# BiphasicBoard.net
KiCad netlist of a schematic drawn in EAGLE
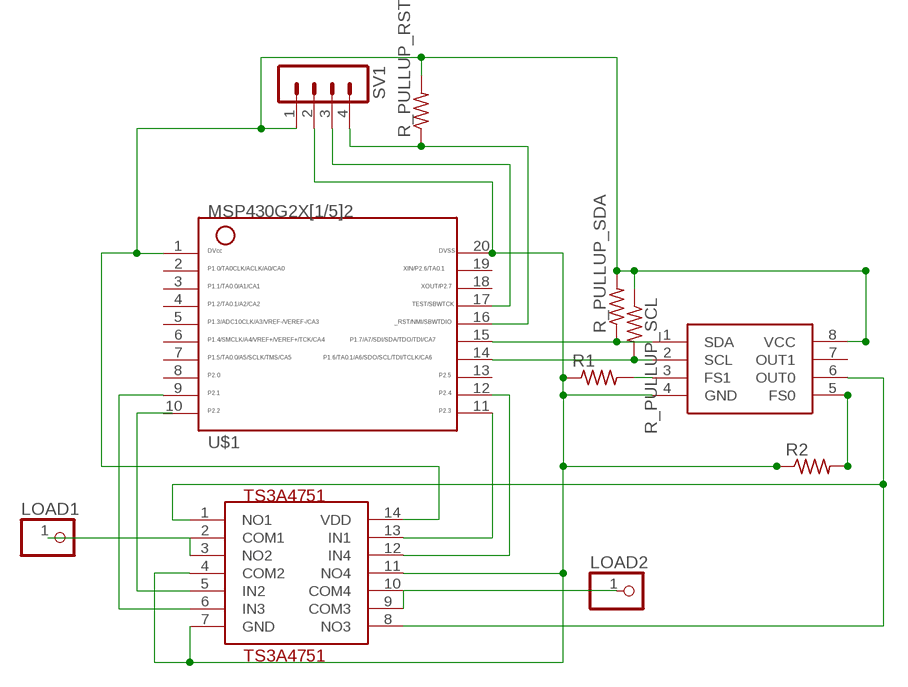
[diagram p0: schematic, sheet 1]

(export (version "E")
  (design (tool "Eeschema 10.0.6"))
  (components
    (comp (ref "DS4432")
      (value "DS4432U+")
      (footprint "eagle-import:DS4432U+")
      (libsource (lib "eagle-import") (part "DS4432U+"))
    )
    (comp (ref "LOAD1")
      (value "PINHD-1X1")
      (footprint "eagle-import:1X01")
      (libsource (lib "eagle-import") (part "PINHD-1X1"))
    )
    (comp (ref "LOAD2")
      (value "PINHD-1X1")
      (footprint "eagle-import:1X01")
      (libsource (lib "eagle-import") (part "PINHD-1X1"))
    )
    (comp (ref "R1")
      (value "R-US_R0603")
      (footprint "eagle-import:R0603")
      (libsource (lib "eagle-import") (part "R-US_R0603"))
    )
    (comp (ref "R2")
      (value "R-US_R0603")
      (footprint "eagle-import:R0603")
      (libsource (lib "eagle-import") (part "R-US_R0603"))
    )
    (comp (ref "R_PULLUP_RST")
      (value "R-US_R0603")
      (footprint "eagle-import:R0603")
      (libsource (lib "eagle-import") (part "R-US_R0603"))
    )
    (comp (ref "R_PULLUP_SCL")
      (value "R-US_R0603")
      (footprint "eagle-import:R0603")
      (libsource (lib "eagle-import") (part "R-US_R0603"))
    )
    (comp (ref "R_PULLUP_SDA")
      (value "R-US_R0603")
      (footprint "eagle-import:R0603")
      (libsource (lib "eagle-import") (part "R-US_R0603"))
    )
    (comp (ref "SV1")
      (value "MA04-1")
      (footprint "eagle-import:MA04-1")
      (libsource (lib "eagle-import") (part "MA04-1"))
    )
    (comp (ref "TS3A4751")
      (value "TS3A4751")
      (footprint "eagle-import:TS3A4751#2")
      (libsource (lib "eagle-import") (part "TS3A4751"))
    )
    (comp (ref "U$1")
      (value "G2X[1/5]2---PW20")
      (footprint "eagle-import:PW20")
      (libsource (lib "eagle-import") (part "G2X[1/5]2---PW20"))
    )
  )
  (nets
    (net (code "1") (name "Net-(DS4432-FS0)") (class "Default")
      (node (ref "DS4432") (pin "5") (pinfunction "FS0_5") (pintype "bidirectional"))
      (node (ref "R2") (pin "2") (pinfunction "2_2") (pintype "passive"))
    )
    (net (code "2") (name "Net-(DS4432-FS1)") (class "Default")
      (node (ref "DS4432") (pin "3") (pinfunction "FS1_3") (pintype "bidirectional"))
      (node (ref "R1") (pin "2") (pinfunction "2_2") (pintype "passive"))
    )
    (net (code "3") (name "Net-(DS4432-GND)") (class "Default")
      (node (ref "DS4432") (pin "4") (pinfunction "GND_4") (pintype "bidirectional"))
      (node (ref "R1") (pin "1") (pinfunction "1_1") (pintype "passive"))
      (node (ref "R2") (pin "1") (pinfunction "1_1") (pintype "passive"))
      (node (ref "SV1") (pin "2") (pinfunction "2_2") (pintype "passive"))
      (node (ref "TS3A4751") (pin "11") (pinfunction "NO4_11") (pintype "bidirectional"))
      (node (ref "TS3A4751") (pin "4") (pinfunction "COM2_4") (pintype "bidirectional"))
      (node (ref "TS3A4751") (pin "7") (pinfunction "GND_7") (pintype "bidirectional"))
      (node (ref "U$1") (pin "20") (pinfunction "20_20") (pintype "bidirectional"))
    )
    (net (code "4") (name "Net-(DS4432-OUT0)") (class "Default")
      (node (ref "DS4432") (pin "6") (pinfunction "OUT0_6") (pintype "bidirectional"))
      (node (ref "TS3A4751") (pin "1") (pinfunction "NO1_1") (pintype "bidirectional"))
      (node (ref "TS3A4751") (pin "8") (pinfunction "NO3_8") (pintype "bidirectional"))
    )
    (net (code "5") (name "Net-(DS4432-SCL)") (class "Default")
      (node (ref "DS4432") (pin "2") (pinfunction "SCL_2") (pintype "bidirectional"))
      (node (ref "R_PULLUP_SCL") (pin "2") (pinfunction "2_2") (pintype "passive"))
      (node (ref "U$1") (pin "14") (pinfunction "14_14") (pintype "bidirectional"))
    )
    (net (code "6") (name "Net-(DS4432-SDA)") (class "Default")
      (node (ref "DS4432") (pin "1") (pinfunction "SDA_1") (pintype "bidirectional"))
      (node (ref "R_PULLUP_SDA") (pin "1") (pinfunction "1_1") (pintype "passive"))
      (node (ref "U$1") (pin "15") (pinfunction "15_15") (pintype "bidirectional"))
    )
    (net (code "7") (name "Net-(DS4432-VCC)") (class "Default")
      (node (ref "DS4432") (pin "8") (pinfunction "VCC_8") (pintype "bidirectional"))
      (node (ref "R_PULLUP_RST") (pin "2") (pinfunction "2_2") (pintype "passive"))
      (node (ref "R_PULLUP_SCL") (pin "1") (pinfunction "1_1") (pintype "passive"))
      (node (ref "R_PULLUP_SDA") (pin "2") (pinfunction "2_2") (pintype "passive"))
      (node (ref "SV1") (pin "1") (pinfunction "1_1") (pintype "passive"))
      (node (ref "TS3A4751") (pin "14") (pinfunction "VDD_14") (pintype "bidirectional"))
      (node (ref "U$1") (pin "1") (pinfunction "1_1") (pintype "bidirectional"))
    )
    (net (code "8") (name "Net-(R_PULLUP_RST-Pad1)") (class "Default")
      (node (ref "R_PULLUP_RST") (pin "1") (pinfunction "1_1") (pintype "passive"))
      (node (ref "SV1") (pin "4") (pinfunction "4_4") (pintype "passive"))
      (node (ref "U$1") (pin "16") (pinfunction "16_16") (pintype "bidirectional"))
    )
    (net (code "9") (name "Net-(SV1-Pad3)") (class "Default")
      (node (ref "SV1") (pin "3") (pinfunction "3_3") (pintype "passive"))
      (node (ref "U$1") (pin "17") (pinfunction "17_17") (pintype "bidirectional"))
    )
    (net (code "10") (name "Net-(TS3A4751-COM1)") (class "Default")
      (node (ref "LOAD1") (pin "1") (pinfunction "1_1") (pintype "passive"))
      (node (ref "TS3A4751") (pin "2") (pinfunction "COM1_2") (pintype "bidirectional"))
      (node (ref "TS3A4751") (pin "3") (pinfunction "NO2_3") (pintype "bidirectional"))
    )
    (net (code "11") (name "Net-(TS3A4751-COM3)") (class "Default")
      (node (ref "LOAD2") (pin "1") (pinfunction "1_1") (pintype "passive"))
      (node (ref "TS3A4751") (pin "10") (pinfunction "COM4_10") (pintype "bidirectional"))
      (node (ref "TS3A4751") (pin "9") (pinfunction "COM3_9") (pintype "bidirectional"))
    )
    (net (code "12") (name "Net-(TS3A4751-IN1)") (class "Default")
      (node (ref "TS3A4751") (pin "13") (pinfunction "IN1_13") (pintype "bidirectional"))
      (node (ref "U$1") (pin "11") (pinfunction "11_11") (pintype "bidirectional"))
    )
    (net (code "13") (name "Net-(TS3A4751-IN2)") (class "Default")
      (node (ref "TS3A4751") (pin "5") (pinfunction "IN2_5") (pintype "bidirectional"))
      (node (ref "U$1") (pin "10") (pinfunction "10_10") (pintype "bidirectional"))
    )
    (net (code "14") (name "Net-(TS3A4751-IN3)") (class "Default")
      (node (ref "TS3A4751") (pin "6") (pinfunction "IN3_6") (pintype "bidirectional"))
      (node (ref "U$1") (pin "9") (pinfunction "9_9") (pintype "bidirectional"))
    )
    (net (code "15") (name "Net-(TS3A4751-IN4)") (class "Default")
      (node (ref "TS3A4751") (pin "12") (pinfunction "IN4_12") (pintype "bidirectional"))
      (node (ref "U$1") (pin "12") (pinfunction "12_12") (pintype "bidirectional"))
    )
    (net (code "16") (name "unconnected-(DS4432-OUT1-Pad7)") (class "Default")
      (node (ref "DS4432") (pin "7") (pinfunction "OUT1_7") (pintype "bidirectional"))
    )
    (net (code "17") (name "unconnected-(U$1-Pad2)") (class "Default")
      (node (ref "U$1") (pin "2") (pinfunction "2_2") (pintype "bidirectional"))
    )
    (net (code "18") (name "unconnected-(U$1-Pad3)") (class "Default")
      (node (ref "U$1") (pin "3") (pinfunction "3_3") (pintype "bidirectional"))
    )
    (net (code "19") (name "unconnected-(U$1-Pad4)") (class "Default")
      (node (ref "U$1") (pin "4") (pinfunction "4_4") (pintype "bidirectional"))
    )
    (net (code "20") (name "unconnected-(U$1-Pad5)") (class "Default")
      (node (ref "U$1") (pin "5") (pinfunction "5_5") (pintype "bidirectional"))
    )
    (net (code "21") (name "unconnected-(U$1-Pad6)") (class "Default")
      (node (ref "U$1") (pin "6") (pinfunction "6_6") (pintype "bidirectional"))
    )
    (net (code "22") (name "unconnected-(U$1-Pad7)") (class "Default")
      (node (ref "U$1") (pin "7") (pinfunction "7_7") (pintype "bidirectional"))
    )
    (net (code "23") (name "unconnected-(U$1-Pad8)") (class "Default")
      (node (ref "U$1") (pin "8") (pinfunction "8_8") (pintype "bidirectional"))
    )
    (net (code "24") (name "unconnected-(U$1-Pad13)") (class "Default")
      (node (ref "U$1") (pin "13") (pinfunction "13_13") (pintype "bidirectional"))
    )
    (net (code "25") (name "unconnected-(U$1-Pad18)") (class "Default")
      (node (ref "U$1") (pin "18") (pinfunction "18_18") (pintype "bidirectional"))
    )
    (net (code "26") (name "unconnected-(U$1-Pad19)") (class "Default")
      (node (ref "U$1") (pin "19") (pinfunction "19_19") (pintype "bidirectional"))
    )
  )
)
